# mk2.net
KiCad netlist of a schematic drawn in EAGLE
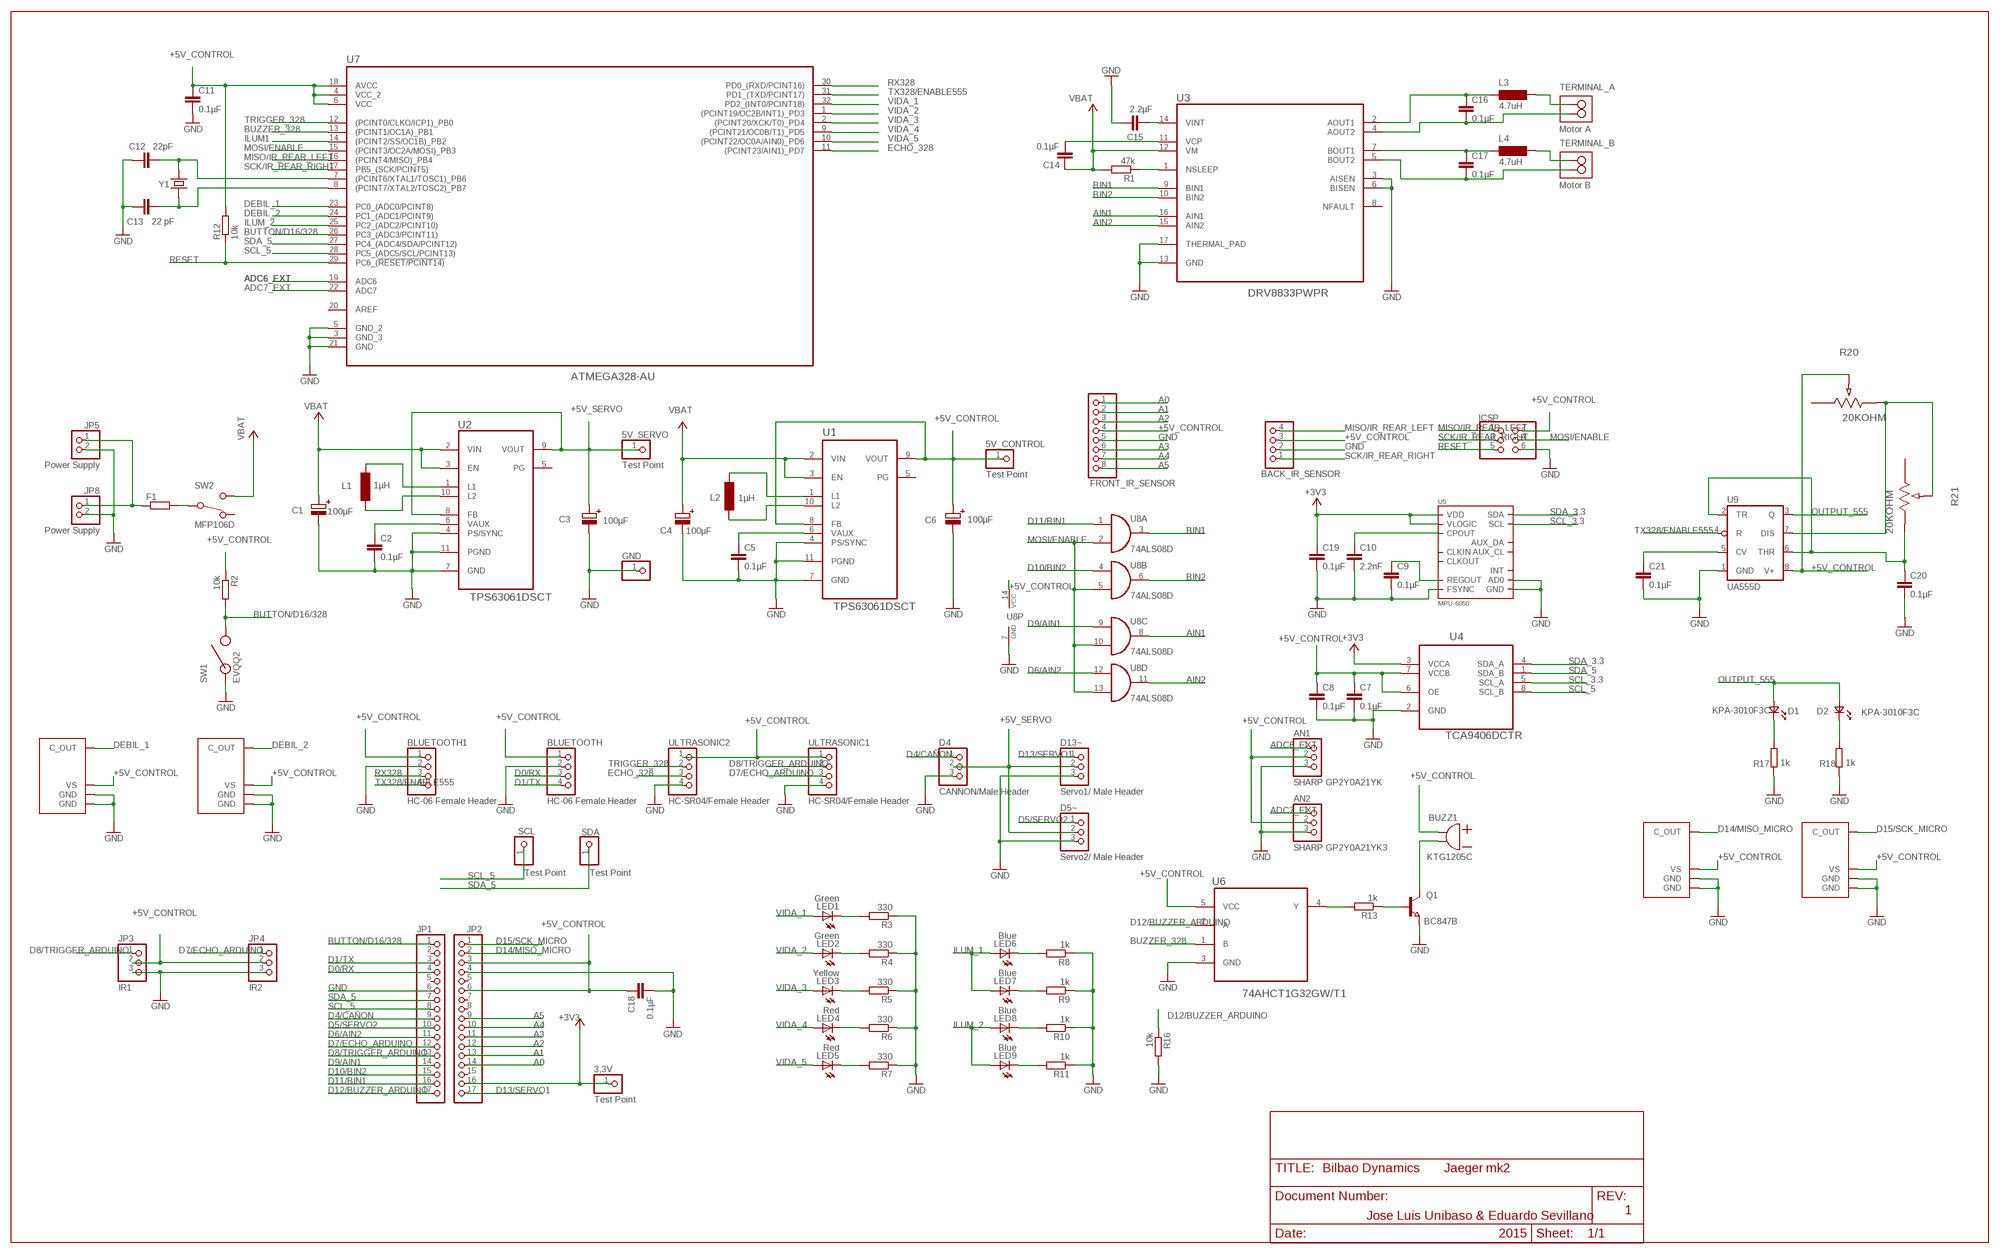
[diagram p0: schematic, sheet 1]

(export (version "E")
  (design (tool "Eeschema 10.0.6"))
  (components
    (comp (ref "3,3V")
      (value "Test Point")
      (footprint "eagle-import:1X01")
      (libsource (lib "eagle-import") (part "PINHD-1X1"))
    )
    (comp (ref "5V_CONTROL")
      (value "Test Point")
      (footprint "eagle-import:1X01")
      (libsource (lib "eagle-import") (part "PINHD-1X1"))
    )
    (comp (ref "5V_SERVO")
      (value "Test Point")
      (footprint "eagle-import:1X01")
      (libsource (lib "eagle-import") (part "PINHD-1X1"))
    )
    (comp (ref "AN1")
      (value "SHARP GP2Y0A21YK")
      (footprint "eagle-import:1X03")
      (libsource (lib "eagle-import") (part "PINHD-1X3"))
    )
    (comp (ref "AN2")
      (value "SHARP GP2Y0A21YK3")
      (footprint "eagle-import:1X03")
      (libsource (lib "eagle-import") (part "PINHD-1X3"))
    )
    (comp (ref "BACK_IR_SENSOR")
      (value "PINHD-1X4")
      (footprint "eagle-import:1X04")
      (libsource (lib "eagle-import") (part "PINHD-1X4"))
    )
    (comp (ref "BLUETOOTH")
      (value "HC-06 Female Header")
      (footprint "eagle-import:1X04")
      (libsource (lib "eagle-import") (part "PINHD-1X4"))
    )
    (comp (ref "BLUETOOTH1")
      (value "HC-06 Female Header")
      (footprint "eagle-import:1X04")
      (libsource (lib "eagle-import") (part "PINHD-1X4"))
    )
    (comp (ref "BUZZ1")
      (value "KTG1205C")
      (footprint "eagle-import:KTG1205C")
      (libsource (lib "eagle-import") (part "KTG1205C"))
    )
    (comp (ref "C1")
      (value "100µF")
      (footprint "eagle-import:EDK107M016A9G")
      (libsource (lib "eagle-import") (part "EDK107M016A9G"))
    )
    (comp (ref "C2")
      (value "0.1µF")
      (footprint "eagle-import:C0805K")
      (libsource (lib "eagle-import") (part "C-EUC0805K"))
    )
    (comp (ref "C3")
      (value "100µF")
      (footprint "eagle-import:EDK107M016A9G")
      (libsource (lib "eagle-import") (part "EDK107M016A9G"))
    )
    (comp (ref "C4")
      (value "100µF")
      (footprint "eagle-import:EDK107M016A9G")
      (libsource (lib "eagle-import") (part "EDK107M016A9G"))
    )
    (comp (ref "C5")
      (value "0.1µF")
      (footprint "eagle-import:C0805K")
      (libsource (lib "eagle-import") (part "C-EUC0805K"))
    )
    (comp (ref "C6")
      (value "100µF")
      (footprint "eagle-import:EDK107M016A9G")
      (libsource (lib "eagle-import") (part "EDK107M016A9G"))
    )
    (comp (ref "C7")
      (value "0.1µF")
      (footprint "eagle-import:C0805")
      (libsource (lib "eagle-import") (part "C-EUC0805"))
    )
    (comp (ref "C8")
      (value "0.1µF")
      (footprint "eagle-import:C0805")
      (libsource (lib "eagle-import") (part "C-EUC0805"))
    )
    (comp (ref "C9")
      (value "0.1µF")
      (footprint "eagle-import:C0805")
      (libsource (lib "eagle-import") (part "C-EUC0805"))
    )
    (comp (ref "C10")
      (value "2.2nF")
      (footprint "eagle-import:C0805")
      (libsource (lib "eagle-import") (part "C-EUC0805"))
    )
    (comp (ref "C11")
      (value "0.1µF")
      (footprint "eagle-import:C0805K")
      (libsource (lib "eagle-import") (part "C-EUC0805K"))
    )
    (comp (ref "C12")
      (value "22pF")
      (footprint "eagle-import:C0805K")
      (libsource (lib "eagle-import") (part "C-EUC0805K"))
    )
    (comp (ref "C13")
      (value "22 pF")
      (footprint "eagle-import:C0805K")
      (libsource (lib "eagle-import") (part "C-EUC0805K"))
    )
    (comp (ref "C14")
      (value "0.1µF")
      (footprint "eagle-import:C0805")
      (libsource (lib "eagle-import") (part "C-EUC0805"))
    )
    (comp (ref "C15")
      (value "2.2µF")
      (footprint "eagle-import:C0805")
      (libsource (lib "eagle-import") (part "C-EUC0805"))
    )
    (comp (ref "C16")
      (value "0.1µF")
      (footprint "eagle-import:C0805")
      (libsource (lib "eagle-import") (part "C-EUC0805"))
    )
    (comp (ref "C17")
      (value "0.1µF")
      (footprint "eagle-import:C0805")
      (libsource (lib "eagle-import") (part "C-EUC0805"))
    )
    (comp (ref "C18")
      (value "0.1µF")
      (footprint "eagle-import:C0805")
      (libsource (lib "eagle-import") (part "C-EUC0805"))
    )
    (comp (ref "C19")
      (value "0.1µF")
      (footprint "eagle-import:C0805")
      (libsource (lib "eagle-import") (part "C-EUC0805"))
    )
    (comp (ref "C20")
      (value "0.1µF")
      (footprint "eagle-import:C0805")
      (libsource (lib "eagle-import") (part "C-EUC0805"))
    )
    (comp (ref "C21")
      (value "0.1µF")
      (footprint "eagle-import:C0805")
      (libsource (lib "eagle-import") (part "C-EUC0805"))
    )
    (comp (ref "D1")
      (value "KPA-3010F3C")
      (footprint "eagle-import:KPA-3010F3C")
      (libsource (lib "eagle-import") (part "KPA-3010F3C"))
    )
    (comp (ref "D2")
      (value "KPA-3010F3C")
      (footprint "eagle-import:KPA-3010F3C")
      (libsource (lib "eagle-import") (part "KPA-3010F3C"))
    )
    (comp (ref "D4")
      (value "CANNON/Male Header")
      (footprint "eagle-import:1X03")
      (libsource (lib "eagle-import") (part "PINHD-1X3"))
    )
    (comp (ref "D5~")
      (value "Servo2/ Male Header")
      (footprint "eagle-import:1X03")
      (libsource (lib "eagle-import") (part "PINHD-1X3"))
    )
    (comp (ref "D13~")
      (value "Servo1/ Male Header")
      (footprint "eagle-import:1X03")
      (libsource (lib "eagle-import") (part "PINHD-1X3"))
    )
    (comp (ref "F1")
      (value "R-EU_R1206")
      (footprint "eagle-import:R1206")
      (libsource (lib "eagle-import") (part "R-EU_R1206"))
    )
    (comp (ref "FRONT_IR_SENSOR")
      (value "PINHD-1X8")
      (footprint "eagle-import:1X08")
      (libsource (lib "eagle-import") (part "PINHD-1X8"))
    )
    (comp (ref "GND")
      (value "PINHD-1X1")
      (footprint "eagle-import:1X01")
      (libsource (lib "eagle-import") (part "PINHD-1X1"))
    )
    (comp (ref "ICSP")
      (value "PINHD-2X3")
      (footprint "eagle-import:2X03")
      (libsource (lib "eagle-import") (part "PINHD-2X3"))
    )
    (comp (ref "IR_REC1")
      (value "TSMP77000TR")
      (footprint "eagle-import:TSMP77000TR")
      (libsource (lib "eagle-import") (part "TSMP77000TR"))
    )
    (comp (ref "IR_REC2")
      (value "TSMP77000TR")
      (footprint "eagle-import:TSMP77000TR")
      (libsource (lib "eagle-import") (part "TSMP77000TR"))
    )
    (comp (ref "IR_REC3")
      (value "TSMP77000TR")
      (footprint "eagle-import:TSMP77000TR")
      (libsource (lib "eagle-import") (part "TSMP77000TR"))
    )
    (comp (ref "IR_REC4")
      (value "TSMP77000TR")
      (footprint "eagle-import:TSMP77000TR")
      (libsource (lib "eagle-import") (part "TSMP77000TR"))
    )
    (comp (ref "JP1")
      (value "PINHD-1X17")
      (footprint "eagle-import:1X17")
      (libsource (lib "eagle-import") (part "PINHD-1X17"))
    )
    (comp (ref "JP2")
      (value "PINHD-1X17")
      (footprint "eagle-import:1X17")
      (libsource (lib "eagle-import") (part "PINHD-1X17"))
    )
    (comp (ref "JP3")
      (value "IR1")
      (footprint "eagle-import:1X03")
      (libsource (lib "eagle-import") (part "PINHD-1X3"))
    )
    (comp (ref "JP4")
      (value "IR2")
      (footprint "eagle-import:1X03")
      (libsource (lib "eagle-import") (part "PINHD-1X3"))
    )
    (comp (ref "JP5")
      (value "Power Supply")
      (footprint "eagle-import:1X02")
      (libsource (lib "eagle-import") (part "PINHD-1X2"))
    )
    (comp (ref "JP8")
      (value "Power Supply")
      (footprint "eagle-import:1X02")
      (libsource (lib "eagle-import") (part "PINHD-1X2"))
    )
    (comp (ref "L1")
      (value "1µH")
      (footprint "eagle-import:MCSDRH73B")
      (libsource (lib "eagle-import") (part "MCSDRH73B"))
    )
    (comp (ref "L2")
      (value "1µH")
      (footprint "eagle-import:MCSDRH73B")
      (libsource (lib "eagle-import") (part "MCSDRH73B"))
    )
    (comp (ref "L3")
      (value "4.7uH")
      (footprint "eagle-import:SRN4012T-4R7M")
      (libsource (lib "eagle-import") (part "SRN4012T-4R7M"))
    )
    (comp (ref "L4")
      (value "4.7uH")
      (footprint "eagle-import:SRN4012T-4R7M")
      (libsource (lib "eagle-import") (part "SRN4012T-4R7M"))
    )
    (comp (ref "LED1")
      (value "Green")
      (footprint "eagle-import:SML0805")
      (libsource (lib "eagle-import") (part "LEDSML0805"))
    )
    (comp (ref "LED2")
      (value "Green")
      (footprint "eagle-import:SML0805")
      (libsource (lib "eagle-import") (part "LEDSML0805"))
    )
    (comp (ref "LED3")
      (value "Yellow")
      (footprint "eagle-import:SML0805")
      (libsource (lib "eagle-import") (part "LEDSML0805"))
    )
    (comp (ref "LED4")
      (value "Red")
      (footprint "eagle-import:SML0805")
      (libsource (lib "eagle-import") (part "LEDSML0805"))
    )
    (comp (ref "LED5")
      (value "Red")
      (footprint "eagle-import:SML0805")
      (libsource (lib "eagle-import") (part "LEDSML0805"))
    )
    (comp (ref "LED6")
      (value "Blue")
      (footprint "eagle-import:SML0805")
      (libsource (lib "eagle-import") (part "LEDSML0805"))
    )
    (comp (ref "LED7")
      (value "Blue")
      (footprint "eagle-import:SML0805")
      (libsource (lib "eagle-import") (part "LEDSML0805"))
    )
    (comp (ref "LED8")
      (value "Blue")
      (footprint "eagle-import:SML0805")
      (libsource (lib "eagle-import") (part "LEDSML0805"))
    )
    (comp (ref "LED9")
      (value "Blue")
      (footprint "eagle-import:SML0805")
      (libsource (lib "eagle-import") (part "LEDSML0805"))
    )
    (comp (ref "Q1")
      (value "BC847B")
      (footprint "eagle-import:SOT23")
      (libsource (lib "eagle-import") (part "NPN-TRANSISTOR_SOT23"))
    )
    (comp (ref "R1")
      (value "47k")
      (footprint "eagle-import:R0805")
      (libsource (lib "eagle-import") (part "R-EU_R0805"))
    )
    (comp (ref "R2")
      (value "10k")
      (footprint "eagle-import:R0805")
      (libsource (lib "eagle-import") (part "R-EU_R0805"))
    )
    (comp (ref "R3")
      (value "330")
      (footprint "eagle-import:R0805")
      (libsource (lib "eagle-import") (part "R-EU_R0805"))
    )
    (comp (ref "R4")
      (value "330")
      (footprint "eagle-import:R0805")
      (libsource (lib "eagle-import") (part "R-EU_R0805"))
    )
    (comp (ref "R5")
      (value "330")
      (footprint "eagle-import:R0805")
      (libsource (lib "eagle-import") (part "R-EU_R0805"))
    )
    (comp (ref "R6")
      (value "330")
      (footprint "eagle-import:R0805")
      (libsource (lib "eagle-import") (part "R-EU_R0805"))
    )
    (comp (ref "R7")
      (value "330")
      (footprint "eagle-import:R0805")
      (libsource (lib "eagle-import") (part "R-EU_R0805"))
    )
    (comp (ref "R8")
      (value "1k")
      (footprint "eagle-import:R0805")
      (libsource (lib "eagle-import") (part "R-EU_R0805"))
    )
    (comp (ref "R9")
      (value "1k")
      (footprint "eagle-import:R0805")
      (libsource (lib "eagle-import") (part "R-EU_R0805"))
    )
    (comp (ref "R10")
      (value "1k")
      (footprint "eagle-import:R0805")
      (libsource (lib "eagle-import") (part "R-EU_R0805"))
    )
    (comp (ref "R11")
      (value "1k")
      (footprint "eagle-import:R0805")
      (libsource (lib "eagle-import") (part "R-EU_R0805"))
    )
    (comp (ref "R12")
      (value "10k")
      (footprint "eagle-import:R0805")
      (libsource (lib "eagle-import") (part "resistor_R-EU_R0805"))
    )
    (comp (ref "R13")
      (value "1k")
      (footprint "eagle-import:R0805")
      (libsource (lib "eagle-import") (part "R-EU_R0805"))
    )
    (comp (ref "R16")
      (value "10k")
      (footprint "eagle-import:R0805")
      (libsource (lib "eagle-import") (part "R-EU_R0805"))
    )
    (comp (ref "R17")
      (value "1k")
      (footprint "eagle-import:R0805")
      (libsource (lib "eagle-import") (part "R-EU_R0805"))
    )
    (comp (ref "R18")
      (value "1k")
      (footprint "eagle-import:R0805")
      (libsource (lib "eagle-import") (part "R-EU_R0805"))
    )
    (comp (ref "R20")
      (value "20KOHM")
      (footprint "eagle-import:POT_EVM2N")
      (fields (field (name "MPN") "EVM2NSX80B24") (field (name "TOLERANCE") "±25 %"))
      (libsource (lib "eagle-import") (part "EVM-2N2NSX80B24"))
    )
    (comp (ref "R21")
      (value "20KOHM")
      (footprint "eagle-import:POT_EVM2N")
      (fields (field (name "MPN") "EVM2NSX80B24") (field (name "TOLERANCE") "±25 %"))
      (libsource (lib "eagle-import") (part "EVM-2N2NSX80B24"))
    )
    (comp (ref "SCL")
      (value "Test Point")
      (footprint "eagle-import:1X01")
      (libsource (lib "eagle-import") (part "PINHD-1X1"))
    )
    (comp (ref "SDA")
      (value "Test Point")
      (footprint "eagle-import:1X01")
      (libsource (lib "eagle-import") (part "PINHD-1X1"))
    )
    (comp (ref "SW1")
      (value "EVQQ2")
      (footprint "eagle-import:EVQQ2")
      (libsource (lib "eagle-import") (part "EVQQ2"))
    )
    (comp (ref "SW2")
      (value "MFP106D")
      (footprint "eagle-import:MFP106D")
      (libsource (lib "eagle-import") (part "MFP106D"))
    )
    (comp (ref "TERMINAL_A")
      (value "Motor A")
      (footprint "eagle-import:CTB30512BK")
      (libsource (lib "eagle-import") (part "CTB30512BK"))
    )
    (comp (ref "TERMINAL_B")
      (value "Motor B")
      (footprint "eagle-import:CTB30512BK")
      (libsource (lib "eagle-import") (part "CTB30512BK"))
    )
    (comp (ref "U1")
      (value "TPS63061DSCT")
      (footprint "eagle-import:SON50P300X300X80-11N")
      (libsource (lib "eagle-import") (part "TPS63061DSCT"))
    )
    (comp (ref "U2")
      (value "TPS63061DSCT")
      (footprint "eagle-import:SON50P300X300X80-11N")
      (libsource (lib "eagle-import") (part "TPS63061DSCT"))
    )
    (comp (ref "U3")
      (value "DRV8833PWPR")
      (footprint "eagle-import:SOP65P640X120-17N")
      (libsource (lib "eagle-import") (part "DRV8833PWPR"))
    )
    (comp (ref "U4")
      (value "TCA9406DCTR")
      (footprint "eagle-import:SOP65P400X130-8N")
      (libsource (lib "eagle-import") (part "TCA9406DCTR"))
    )
    (comp (ref "U5")
      (value "MPU-6050")
      (footprint "eagle-import:QFN.24.4X4")
      (libsource (lib "eagle-import") (part "MPU-6050"))
    )
    (comp (ref "U6")
      (value "74AHCT1G32GW/T1")
      (footprint "eagle-import:SOT65P210X110-5N")
      (libsource (lib "eagle-import") (part "74AHCT1G32GW/T1"))
    )
    (comp (ref "U7")
      (value "ATMEGA328-AU")
      (footprint "eagle-import:QFP80P900X900X120-32N")
      (libsource (lib "eagle-import") (part "ATMEGA328-AU"))
    )
    (comp (ref "U8")
      (value "74ALS08D")
      (footprint "eagle-import:SO14")
      (libsource (lib "eagle-import") (part "7408DALS"))
    )
    (comp (ref "U9")
      (value "UA555D")
      (footprint "eagle-import:SO08")
      (libsource (lib "eagle-import") (part "555DUA"))
    )
    (comp (ref "ULTRASONIC1")
      (value "HC-SR04/Female Header")
      (footprint "eagle-import:1X04")
      (libsource (lib "eagle-import") (part "PINHD-1X4"))
    )
    (comp (ref "ULTRASONIC2")
      (value "HC-SR04/Female Header")
      (footprint "eagle-import:1X04")
      (libsource (lib "eagle-import") (part "PINHD-1X4"))
    )
    (comp (ref "Y1")
      (value "E3SB16.0000F09G11AE")
      (footprint "eagle-import:E3SB16.0000F09G11A")
      (libsource (lib "eagle-import") (part "E3SB16.0000F09G11AE"))
    )
  )
  (nets
    (net (code "1") (name "+3V3") (class "Default")
      (node (ref "3,3V") (pin "1") (pinfunction "1_1") (pintype "passive"))
      (node (ref "JP2") (pin "16") (pinfunction "16_16") (pintype "passive"))
      (node (ref "U4") (pin "3") (pinfunction "VCCA_3") (pintype "power_in"))
    )
    (net (code "2") (name "/+5V_CONTROL") (class "Default")
      (node (ref "5V_CONTROL") (pin "1") (pinfunction "1_1") (pintype "passive"))
      (node (ref "AN1") (pin "2") (pinfunction "2_2") (pintype "passive"))
      (node (ref "AN2") (pin "2") (pinfunction "2_2") (pintype "passive"))
      (node (ref "BACK_IR_SENSOR") (pin "3") (pinfunction "3_3") (pintype "passive"))
      (node (ref "BLUETOOTH") (pin "1") (pinfunction "1_1") (pintype "passive"))
      (node (ref "BLUETOOTH1") (pin "1") (pinfunction "1_1") (pintype "passive"))
      (node (ref "BUZZ1") (pin "+") (pinfunction "+_+") (pintype "passive"))
      (node (ref "C11") (pin "1") (pinfunction "1_1") (pintype "passive"))
      (node (ref "C18") (pin "1") (pinfunction "1_1") (pintype "passive"))
      (node (ref "C6") (pin "1") (pinfunction "1_1") (pintype "passive"))
      (node (ref "C7") (pin "1") (pinfunction "1_1") (pintype "passive"))
      (node (ref "C8") (pin "1") (pinfunction "1_1") (pintype "passive"))
      (node (ref "FRONT_IR_SENSOR") (pin "4") (pinfunction "4_4") (pintype "passive"))
      (node (ref "ICSP") (pin "2") (pinfunction "2_2") (pintype "passive"))
      (node (ref "IR_REC1") (pin "2") (pinfunction "VS_2") (pintype "power_in"))
      (node (ref "IR_REC2") (pin "2") (pinfunction "VS_2") (pintype "power_in"))
      (node (ref "IR_REC3") (pin "2") (pinfunction "VS_2") (pintype "power_in"))
      (node (ref "IR_REC4") (pin "2") (pinfunction "VS_2") (pintype "power_in"))
      (node (ref "JP2") (pin "3") (pinfunction "3_3") (pintype "passive"))
      (node (ref "JP2") (pin "6") (pinfunction "6_6") (pintype "passive"))
      (node (ref "JP3") (pin "2") (pinfunction "2_2") (pintype "passive"))
      (node (ref "JP4") (pin "2") (pinfunction "2_2") (pintype "passive"))
      (node (ref "R12") (pin "2") (pinfunction "2_2") (pintype "passive"))
      (node (ref "R2") (pin "1") (pinfunction "1_1") (pintype "passive"))
      (node (ref "R20") (pin "2") (pinfunction "2_2") (pintype "passive"))
      (node (ref "U1") (pin "8") (pinfunction "FB_8") (pintype "input"))
      (node (ref "U1") (pin "9") (pinfunction "VOUT_9") (pintype "output"))
      (node (ref "U4") (pin "6") (pinfunction "OE_6") (pintype "input"))
      (node (ref "U4") (pin "7") (pinfunction "VCCB_7") (pintype "power_in"))
      (node (ref "U6") (pin "5") (pinfunction "VCC_5") (pintype "power_in"))
      (node (ref "U7") (pin "18") (pinfunction "AVCC_18") (pintype "power_in"))
      (node (ref "U7") (pin "4") (pinfunction "VCC_2_4") (pintype "power_in"))
      (node (ref "U7") (pin "6") (pinfunction "VCC_6") (pintype "power_in"))
      (node (ref "U8") (pin "14") (pinfunction "VCC_14") (pintype "power_in"))
      (node (ref "U9") (pin "8") (pinfunction "V+_8") (pintype "power_in"))
      (node (ref "ULTRASONIC1") (pin "1") (pinfunction "1_1") (pintype "passive"))
      (node (ref "ULTRASONIC2") (pin "1") (pinfunction "1_1") (pintype "passive"))
    )
    (net (code "3") (name "/+5V_SERVO") (class "Default")
      (node (ref "5V_SERVO") (pin "1") (pinfunction "1_1") (pintype "passive"))
      (node (ref "C3") (pin "1") (pinfunction "1_1") (pintype "passive"))
      (node (ref "D13~") (pin "2") (pinfunction "2_2") (pintype "passive"))
      (node (ref "D4") (pin "2") (pinfunction "2_2") (pintype "passive"))
      (node (ref "D5~") (pin "2") (pinfunction "2_2") (pintype "passive"))
      (node (ref "U2") (pin "8") (pinfunction "FB_8") (pintype "input"))
      (node (ref "U2") (pin "9") (pinfunction "VOUT_9") (pintype "output"))
    )
    (net (code "4") (name "/A0") (class "Default")
      (node (ref "FRONT_IR_SENSOR") (pin "1") (pinfunction "1_1") (pintype "passive"))
      (node (ref "JP2") (pin "14") (pinfunction "14_14") (pintype "passive"))
    )
    (net (code "5") (name "/A1") (class "Default")
      (node (ref "FRONT_IR_SENSOR") (pin "2") (pinfunction "2_2") (pintype "passive"))
      (node (ref "JP2") (pin "13") (pinfunction "13_13") (pintype "passive"))
    )
    (net (code "6") (name "/A2") (class "Default")
      (node (ref "FRONT_IR_SENSOR") (pin "3") (pinfunction "3_3") (pintype "passive"))
      (node (ref "JP2") (pin "12") (pinfunction "12_12") (pintype "passive"))
    )
    (net (code "7") (name "/A3") (class "Default")
      (node (ref "FRONT_IR_SENSOR") (pin "6") (pinfunction "6_6") (pintype "passive"))
      (node (ref "JP2") (pin "11") (pinfunction "11_11") (pintype "passive"))
    )
    (net (code "8") (name "/A4") (class "Default")
      (node (ref "FRONT_IR_SENSOR") (pin "7") (pinfunction "7_7") (pintype "passive"))
      (node (ref "JP2") (pin "10") (pinfunction "10_10") (pintype "passive"))
    )
    (net (code "9") (name "/A5") (class "Default")
      (node (ref "FRONT_IR_SENSOR") (pin "8") (pinfunction "8_8") (pintype "passive"))
      (node (ref "JP2") (pin "9") (pinfunction "9_9") (pintype "passive"))
    )
    (net (code "10") (name "/ADC6_EXT") (class "Default")
      (node (ref "AN1") (pin "1") (pinfunction "1_1") (pintype "passive"))
      (node (ref "U7") (pin "19") (pinfunction "ADC6_19") (pintype "input"))
    )
    (net (code "11") (name "/ADC7_EXT") (class "Default")
      (node (ref "AN2") (pin "1") (pinfunction "1_1") (pintype "passive"))
      (node (ref "U7") (pin "22") (pinfunction "ADC7_22") (pintype "input"))
    )
    (net (code "12") (name "/AIN1") (class "Default")
      (node (ref "U3") (pin "16") (pinfunction "AIN1_16") (pintype "input"))
      (node (ref "U8") (pin "8") (pinfunction "O_8") (pintype "output"))
    )
    (net (code "13") (name "/AIN2") (class "Default")
      (node (ref "U3") (pin "15") (pinfunction "AIN2_15") (pintype "input"))
      (node (ref "U8") (pin "11") (pinfunction "O_11") (pintype "output"))
    )
    (net (code "14") (name "/BIN1") (class "Default")
      (node (ref "U3") (pin "9") (pinfunction "BIN1_9") (pintype "input"))
      (node (ref "U8") (pin "3") (pinfunction "O_3") (pintype "output"))
    )
    (net (code "15") (name "/BIN2") (class "Default")
      (node (ref "U3") (pin "10") (pinfunction "BIN2_10") (pintype "input"))
      (node (ref "U8") (pin "6") (pinfunction "O_6") (pintype "output"))
    )
    (net (code "16") (name "/BUTTON{slash}D16{slash}328") (class "Default")
      (node (ref "JP1") (pin "1") (pinfunction "1_1") (pintype "passive"))
      (node (ref "R2") (pin "2") (pinfunction "2_2") (pintype "passive"))
      (node (ref "SW1") (pin "P$1") (pinfunction "P$2_P$1") (pintype "passive"))
      (node (ref "SW1") (pin "P$4") (pinfunction "P$2_P$4") (pintype "passive"))
      (node (ref "U7") (pin "26") (pinfunction "PC3_(ADC3/PCINT11)_26") (pintype "bidirectional"))
    )
    (net (code "17") (name "/BUZZER_328") (class "Default")
      (node (ref "U6") (pin "1") (pinfunction "B_1") (pintype "input"))
      (node (ref "U7") (pin "13") (pinfunction "(PCINT1/OC1A)_PB1_13") (pintype "bidirectional"))
    )
    (net (code "18") (name "/D0{slash}RX") (class "Default")
      (node (ref "BLUETOOTH") (pin "3") (pinfunction "3_3") (pintype "passive"))
      (node (ref "JP1") (pin "4") (pinfunction "4_4") (pintype "passive"))
    )
    (net (code "19") (name "/D1{slash}TX") (class "Default")
      (node (ref "BLUETOOTH") (pin "4") (pinfunction "4_4") (pintype "passive"))
      (node (ref "JP1") (pin "3") (pinfunction "3_3") (pintype "passive"))
    )
    (net (code "20") (name "/D4{slash}CAÑON") (class "Default")
      (node (ref "D4") (pin "1") (pinfunction "1_1") (pintype "passive"))
      (node (ref "JP1") (pin "9") (pinfunction "9_9") (pintype "passive"))
    )
    (net (code "21") (name "/D5{slash}SERVO2") (class "Default")
      (node (ref "D5~") (pin "1") (pinfunction "1_1") (pintype "passive"))
      (node (ref "JP1") (pin "10") (pinfunction "10_10") (pintype "passive"))
    )
    (net (code "22") (name "/D6{slash}AIN2") (class "Default")
      (node (ref "JP1") (pin "11") (pinfunction "11_11") (pintype "passive"))
      (node (ref "U8") (pin "12") (pinfunction "I0_12") (pintype "input"))
    )
    (net (code "23") (name "/D7{slash}ECHO_ARDUINO") (class "Default")
      (node (ref "JP1") (pin "12") (pinfunction "12_12") (pintype "passive"))
      (node (ref "JP4") (pin "1") (pinfunction "1_1") (pintype "passive"))
      (node (ref "ULTRASONIC1") (pin "3") (pinfunction "3_3") (pintype "passive"))
    )
    (net (code "24") (name "/D8{slash}TRIGGER_ARDUINO") (class "Default")
      (node (ref "JP1") (pin "13") (pinfunction "13_13") (pintype "passive"))
      (node (ref "JP3") (pin "1") (pinfunction "1_1") (pintype "passive"))
      (node (ref "ULTRASONIC1") (pin "2") (pinfunction "2_2") (pintype "passive"))
    )
    (net (code "25") (name "/D9{slash}AIN1") (class "Default")
      (node (ref "JP1") (pin "14") (pinfunction "14_14") (pintype "passive"))
      (node (ref "U8") (pin "9") (pinfunction "I0_9") (pintype "input"))
    )
    (net (code "26") (name "/D10{slash}BIN2") (class "Default")
      (node (ref "JP1") (pin "15") (pinfunction "15_15") (pintype "passive"))
      (node (ref "U8") (pin "4") (pinfunction "I0_4") (pintype "input"))
    )
    (net (code "27") (name "/D11{slash}BIN1") (class "Default")
      (node (ref "JP1") (pin "16") (pinfunction "16_16") (pintype "passive"))
      (node (ref "U8") (pin "1") (pinfunction "I0_1") (pintype "input"))
    )
    (net (code "28") (name "/D12{slash}BUZZER_ARDUINO") (class "Default")
      (node (ref "JP1") (pin "17") (pinfunction "17_17") (pintype "passive"))
      (node (ref "R16") (pin "1") (pinfunction "1_1") (pintype "passive"))
      (node (ref "U6") (pin "2") (pinfunction "A_2") (pintype "input"))
    )
    (net (code "29") (name "/D13{slash}SERVO1") (class "Default")
      (node (ref "D13~") (pin "1") (pinfunction "1_1") (pintype "passive"))
      (node (ref "JP2") (pin "17") (pinfunction "17_17") (pintype "passive"))
    )
    (net (code "30") (name "/D14{slash}MISO_MICRO") (class "Default")
      (node (ref "IR_REC1") (pin "3") (pinfunction "C_OUT_3") (pintype "bidirectional"))
      (node (ref "JP2") (pin "2") (pinfunction "2_2") (pintype "passive"))
    )
    (net (code "31") (name "/D15{slash}SCK_MICRO") (class "Default")
      (node (ref "IR_REC2") (pin "3") (pinfunction "C_OUT_3") (pintype "bidirectional"))
      (node (ref "JP2") (pin "1") (pinfunction "1_1") (pintype "passive"))
    )
    (net (code "32") (name "/DEBIL_1") (class "Default")
      (node (ref "IR_REC3") (pin "3") (pinfunction "C_OUT_3") (pintype "bidirectional"))
      (node (ref "U7") (pin "23") (pinfunction "PC0_(ADC0/PCINT8)_23") (pintype "bidirectional"))
    )
    (net (code "33") (name "/DEBIL_2") (class "Default")
      (node (ref "IR_REC4") (pin "3") (pinfunction "C_OUT_3") (pintype "bidirectional"))
      (node (ref "U7") (pin "24") (pinfunction "PC1_(ADC1/PCINT9)_24") (pintype "bidirectional"))
    )
    (net (code "34") (name "/ECHO_328") (class "Default")
      (node (ref "U7") (pin "11") (pinfunction "(PCINT23/AIN1)_PD7_11") (pintype "bidirectional"))
      (node (ref "ULTRASONIC2") (pin "3") (pinfunction "3_3") (pintype "passive"))
    )
    (net (code "35") (name "/ILUM1") (class "Default")
      (node (ref "U7") (pin "14") (pinfunction "(PCINT2/SS/OC1B)_PB2_14") (pintype "bidirectional"))
    )
    (net (code "36") (name "/ILUM_1") (class "Default")
      (node (ref "LED6") (pin "A") (pinfunction "A_A") (pintype "passive"))
      (node (ref "LED7") (pin "A") (pinfunction "A_A") (pintype "passive"))
    )
    (net (code "37") (name "/ILUM_2") (class "Default")
      (node (ref "LED8") (pin "A") (pinfunction "A_A") (pintype "passive"))
      (node (ref "LED9") (pin "A") (pinfunction "A_A") (pintype "passive"))
      (node (ref "U7") (pin "25") (pinfunction "PC2_(ADC2/PCINT10)_25") (pintype "bidirectional"))
    )
    (net (code "38") (name "/MISO{slash}IR_REAR_LEFT") (class "Default")
      (node (ref "BACK_IR_SENSOR") (pin "4") (pinfunction "4_4") (pintype "passive"))
      (node (ref "ICSP") (pin "1") (pinfunction "1_1") (pintype "passive"))
      (node (ref "U7") (pin "16") (pinfunction "(PCINT4/MISO)_PB4_16") (pintype "bidirectional"))
    )
    (net (code "39") (name "/MOSI{slash}ENABLE") (class "Default")
      (node (ref "ICSP") (pin "4") (pinfunction "4_4") (pintype "passive"))
      (node (ref "U7") (pin "15") (pinfunction "(PCINT3/OC2A/MOSI)_PB3_15") (pintype "bidirectional"))
      (node (ref "U8") (pin "10") (pinfunction "I1_10") (pintype "input"))
      (node (ref "U8") (pin "13") (pinfunction "I1_13") (pintype "input"))
      (node (ref "U8") (pin "2") (pinfunction "I1_2") (pintype "input"))
      (node (ref "U8") (pin "5") (pinfunction "I1_5") (pintype "input"))
    )
    (net (code "40") (name "/OUTPUT_555") (class "Default")
      (node (ref "D1") (pin "A") (pinfunction "A_A") (pintype "passive"))
      (node (ref "D2") (pin "A") (pinfunction "A_A") (pintype "passive"))
      (node (ref "U9") (pin "3") (pinfunction "Q_3") (pintype "output"))
    )
    (net (code "41") (name "/RESET") (class "Default")
      (node (ref "ICSP") (pin "5") (pinfunction "5_5") (pintype "passive"))
      (node (ref "R12") (pin "1") (pinfunction "1_1") (pintype "passive"))
      (node (ref "U7") (pin "29") (pinfunction "PC6_(~{RESET/PCINT14})_29") (pintype "bidirectional"))
    )
    (net (code "42") (name "/RX328") (class "Default")
      (node (ref "BLUETOOTH1") (pin "3") (pinfunction "3_3") (pintype "passive"))
      (node (ref "U7") (pin "30") (pinfunction "PD0_(RXD/PCINT16)_30") (pintype "bidirectional"))
    )
    (net (code "43") (name "/SCK{slash}IR_REAR_RIGHT") (class "Default")
      (node (ref "BACK_IR_SENSOR") (pin "1") (pinfunction "1_1") (pintype "passive"))
      (node (ref "ICSP") (pin "3") (pinfunction "3_3") (pintype "passive"))
      (node (ref "U7") (pin "17") (pinfunction "PB5_(SCK/PCINT5)_17") (pintype "bidirectional"))
    )
    (net (code "44") (name "/SCL_3.3") (class "Default")
      (node (ref "U4") (pin "5") (pinfunction "SCL_A_5") (pintype "bidirectional"))
      (node (ref "U5") (pin "23") (pinfunction "SCL_23") (pintype "bidirectional"))
    )
    (net (code "45") (name "/SCL_5") (class "Default")
      (node (ref "JP1") (pin "8") (pinfunction "8_8") (pintype "passive"))
      (node (ref "SCL") (pin "1") (pinfunction "1_1") (pintype "passive"))
      (node (ref "U4") (pin "8") (pinfunction "SCL_B_8") (pintype "bidirectional"))
      (node (ref "U7") (pin "28") (pinfunction "PC5_(ADC5/SCL/PCINT13)_28") (pintype "bidirectional"))
    )
    (net (code "46") (name "/SDA_3.3") (class "Default")
      (node (ref "U4") (pin "4") (pinfunction "SDA_A_4") (pintype "bidirectional"))
      (node (ref "U5") (pin "24") (pinfunction "SDA_24") (pintype "bidirectional"))
    )
    (net (code "47") (name "/SDA_5") (class "Default")
      (node (ref "JP1") (pin "7") (pinfunction "7_7") (pintype "passive"))
      (node (ref "SDA") (pin "1") (pinfunction "1_1") (pintype "passive"))
      (node (ref "U4") (pin "1") (pinfunction "SDA_B_1") (pintype "bidirectional"))
      (node (ref "U7") (pin "27") (pinfunction "PC4_(ADC4/SDA/PCINT12)_27") (pintype "bidirectional"))
    )
    (net (code "48") (name "/TRIGGER_328") (class "Default")
      (node (ref "U7") (pin "12") (pinfunction "(PCINT0/CLKO/ICP1)_PB0_12") (pintype "bidirectional"))
      (node (ref "ULTRASONIC2") (pin "2") (pinfunction "2_2") (pintype "passive"))
    )
    (net (code "49") (name "/TX328{slash}ENABLE555") (class "Default")
      (node (ref "BLUETOOTH1") (pin "4") (pinfunction "4_4") (pintype "passive"))
      (node (ref "U7") (pin "31") (pinfunction "PD1_(TXD/PCINT17)_31") (pintype "bidirectional"))
      (node (ref "U9") (pin "4") (pinfunction "R_4") (pintype "input"))
    )
    (net (code "50") (name "/VIDA_1") (class "Default")
      (node (ref "LED1") (pin "A") (pinfunction "A_A") (pintype "passive"))
      (node (ref "U7") (pin "32") (pinfunction "PD2_(INT0/PCINT18)_32") (pintype "bidirectional"))
    )
    (net (code "51") (name "/VIDA_2") (class "Default")
      (node (ref "LED2") (pin "A") (pinfunction "A_A") (pintype "passive"))
      (node (ref "U7") (pin "1") (pinfunction "(PCINT19/OC2B/INT1)_PD3_1") (pintype "bidirectional"))
    )
    (net (code "52") (name "/VIDA_3") (class "Default")
      (node (ref "LED3") (pin "A") (pinfunction "A_A") (pintype "passive"))
      (node (ref "U7") (pin "2") (pinfunction "(PCINT20/XCK/T0)_PD4_2") (pintype "bidirectional"))
    )
    (net (code "53") (name "/VIDA_4") (class "Default")
      (node (ref "LED4") (pin "A") (pinfunction "A_A") (pintype "passive"))
      (node (ref "U7") (pin "9") (pinfunction "(PCINT21/OC0B/T1)_PD5_9") (pintype "bidirectional"))
    )
    (net (code "54") (name "/VIDA_5") (class "Default")
      (node (ref "LED5") (pin "A") (pinfunction "A_A") (pintype "passive"))
      (node (ref "U7") (pin "10") (pinfunction "(PCINT22/OC0A/AIN0)_PD6_10") (pintype "bidirectional"))
    )
    (net (code "55") (name "GND") (class "Default")
      (node (ref "AN1") (pin "3") (pinfunction "3_3") (pintype "passive"))
      (node (ref "AN2") (pin "3") (pinfunction "3_3") (pintype "passive"))
      (node (ref "BACK_IR_SENSOR") (pin "2") (pinfunction "2_2") (pintype "passive"))
      (node (ref "BLUETOOTH") (pin "2") (pinfunction "2_2") (pintype "passive"))
      (node (ref "BLUETOOTH1") (pin "2") (pinfunction "2_2") (pintype "passive"))
      (node (ref "C1") (pin "2") (pinfunction "2_2") (pintype "passive"))
      (node (ref "C10") (pin "2") (pinfunction "2_2") (pintype "passive"))
      (node (ref "C11") (pin "2") (pinfunction "2_2") (pintype "passive"))
      (node (ref "C12") (pin "1") (pinfunction "1_1") (pintype "passive"))
      (node (ref "C13") (pin "1") (pinfunction "1_1") (pintype "passive"))
      (node (ref "C15") (pin "1") (pinfunction "1_1") (pintype "passive"))
      (node (ref "C18") (pin "2") (pinfunction "2_2") (pintype "passive"))
      (node (ref "C19") (pin "2") (pinfunction "2_2") (pintype "passive"))
      (node (ref "C2") (pin "2") (pinfunction "2_2") (pintype "passive"))
      (node (ref "C20") (pin "2") (pinfunction "2_2") (pintype "passive"))
      (node (ref "C21") (pin "2") (pinfunction "2_2") (pintype "passive"))
      (node (ref "C3") (pin "2") (pinfunction "2_2") (pintype "passive"))
      (node (ref "C4") (pin "2") (pinfunction "2_2") (pintype "passive"))
      (node (ref "C5") (pin "2") (pinfunction "2_2") (pintype "passive"))
      (node (ref "C6") (pin "2") (pinfunction "2_2") (pintype "passive"))
      (node (ref "C7") (pin "2") (pinfunction "2_2") (pintype "passive"))
      (node (ref "C8") (pin "2") (pinfunction "2_2") (pintype "passive"))
      (node (ref "C9") (pin "2") (pinfunction "2_2") (pintype "passive"))
      (node (ref "D13~") (pin "3") (pinfunction "3_3") (pintype "passive"))
      (node (ref "D4") (pin "3") (pinfunction "3_3") (pintype "passive"))
      (node (ref "D5~") (pin "3") (pinfunction "3_3") (pintype "passive"))
      (node (ref "FRONT_IR_SENSOR") (pin "5") (pinfunction "5_5") (pintype "passive"))
      (node (ref "GND") (pin "1") (pinfunction "1_1") (pintype "passive"))
      (node (ref "ICSP") (pin "6") (pinfunction "6_6") (pintype "passive"))
      (node (ref "IR_REC1") (pin "1") (pinfunction "GND_1") (pintype "power_in"))
      (node (ref "IR_REC1") (pin "4") (pinfunction "GND_4") (pintype "power_in"))
      (node (ref "IR_REC2") (pin "1") (pinfunction "GND_1") (pintype "power_in"))
      (node (ref "IR_REC2") (pin "4") (pinfunction "GND_4") (pintype "power_in"))
      (node (ref "IR_REC3") (pin "1") (pinfunction "GND_1") (pintype "power_in"))
      (node (ref "IR_REC3") (pin "4") (pinfunction "GND_4") (pintype "power_in"))
      (node (ref "IR_REC4") (pin "1") (pinfunction "GND_1") (pintype "power_in"))
      (node (ref "IR_REC4") (pin "4") (pinfunction "GND_4") (pintype "power_in"))
      (node (ref "JP1") (pin "6") (pinfunction "6_6") (pintype "passive"))
      (node (ref "JP2") (pin "4") (pinfunction "4_4") (pintype "passive"))
      (node (ref "JP3") (pin "3") (pinfunction "3_3") (pintype "passive"))
      (node (ref "JP4") (pin "3") (pinfunction "3_3") (pintype "passive"))
      (node (ref "JP5") (pin "2") (pinfunction "2_2") (pintype "passive"))
      (node (ref "JP8") (pin "2") (pinfunction "2_2") (pintype "passive"))
      (node (ref "Q1") (pin "2") (pinfunction "E_2") (pintype "passive"))
      (node (ref "R10") (pin "1") (pinfunction "1_1") (pintype "passive"))
      (node (ref "R11") (pin "1") (pinfunction "1_1") (pintype "passive"))
      (node (ref "R16") (pin "2") (pinfunction "2_2") (pintype "passive"))
      (node (ref "R17") (pin "2") (pinfunction "2_2") (pintype "passive"))
      (node (ref "R18") (pin "2") (pinfunction "2_2") (pintype "passive"))
      (node (ref "R3") (pin "1") (pinfunction "1_1") (pintype "passive"))
      (node (ref "R4") (pin "1") (pinfunction "1_1") (pintype "passive"))
      (node (ref "R5") (pin "1") (pinfunction "1_1") (pintype "passive"))
      (node (ref "R6") (pin "1") (pinfunction "1_1") (pintype "passive"))
      (node (ref "R7") (pin "1") (pinfunction "1_1") (pintype "passive"))
      (node (ref "R8") (pin "1") (pinfunction "1_1") (pintype "passive"))
      (node (ref "R9") (pin "1") (pinfunction "1_1") (pintype "passive"))
      (node (ref "SW1") (pin "P$2") (pinfunction "P$1_P$2") (pintype "passive"))
      (node (ref "SW1") (pin "P$3") (pinfunction "P$1_P$3") (pintype "passive"))
      (node (ref "U1") (pin "11") (pinfunction "PGND_11") (pintype "passive"))
      (node (ref "U1") (pin "4") (pinfunction "PS/SYNC_4") (pintype "input"))
      (node (ref "U1") (pin "7") (pinfunction "GND_7") (pintype "passive"))
      (node (ref "U2") (pin "11") (pinfunction "PGND_11") (pintype "passive"))
      (node (ref "U2") (pin "4") (pinfunction "PS/SYNC_4") (pintype "input"))
      (node (ref "U2") (pin "7") (pinfunction "GND_7") (pintype "passive"))
      (node (ref "U3") (pin "13") (pinfunction "GND_13") (pintype "passive"))
      (node (ref "U3") (pin "17") (pinfunction "THERMAL_PAD_17") (pintype "passive"))
      (node (ref "U3") (pin "3") (pinfunction "AISEN_3") (pintype "bidirectional"))
      (node (ref "U3") (pin "6") (pinfunction "BISEN_6") (pintype "bidirectional"))
      (node (ref "U4") (pin "2") (pinfunction "GND_2") (pintype "power_in"))
      (node (ref "U5") (pin "11") (pinfunction "FSYNC_11") (pintype "bidirectional"))
      (node (ref "U5") (pin "18") (pinfunction "GND_18") (pintype "bidirectional"))
      (node (ref "U5") (pin "9") (pinfunction "AD0_9") (pintype "bidirectional"))
      (node (ref "U6") (pin "3") (pinfunction "GND_3") (pintype "passive"))
      (node (ref "U7") (pin "21") (pinfunction "GND_21") (pintype "passive"))
      (node (ref "U7") (pin "3") (pinfunction "GND_3_3") (pintype "passive"))
      (node (ref "U7") (pin "5") (pinfunction "GND_2_5") (pintype "passive"))
      (node (ref "U8") (pin "7") (pinfunction "GND_7") (pintype "power_in"))
      (node (ref "U9") (pin "1") (pinfunction "GND_1") (pintype "power_in"))
      (node (ref "ULTRASONIC1") (pin "4") (pinfunction "4_4") (pintype "passive"))
      (node (ref "ULTRASONIC2") (pin "4") (pinfunction "4_4") (pintype "passive"))
    )
    (net (code "56") (name "Net-(D1-PadC)") (class "Default")
      (node (ref "D1") (pin "C") (pinfunction "C_C") (pintype "passive"))
      (node (ref "R17") (pin "1") (pinfunction "1_1") (pintype "passive"))
    )
    (net (code "57") (name "Net-(D2-PadC)") (class "Default")
      (node (ref "D2") (pin "C") (pinfunction "C_C") (pintype "passive"))
      (node (ref "R18") (pin "1") (pinfunction "1_1") (pintype "passive"))
    )
    (net (code "58") (name "Net-(F1-Pad1)") (class "Default")
      (node (ref "F1") (pin "1") (pinfunction "1_1") (pintype "passive"))
      (node (ref "JP5") (pin "1") (pinfunction "1_1") (pintype "passive"))
      (node (ref "JP8") (pin "1") (pinfunction "1_1") (pintype "passive"))
    )
    (net (code "59") (name "Net-(F1-Pad2)") (class "Default")
      (node (ref "F1") (pin "2") (pinfunction "2_2") (pintype "passive"))
      (node (ref "SW2") (pin "COM") (pinfunction "COM_COM") (pintype "passive"))
    )
    (net (code "60") (name "Net-(L1-P$1)") (class "Default")
      (node (ref "L1") (pin "1") (pinfunction "P$1_1") (pintype "passive"))
      (node (ref "U2") (pin "10") (pinfunction "L2_10") (pintype "input"))
    )
    (net (code "61") (name "Net-(L1-P$2)") (class "Default")
      (node (ref "L1") (pin "2") (pinfunction "P$2_2") (pintype "passive"))
      (node (ref "U2") (pin "1") (pinfunction "L1_1") (pintype "input"))
    )
    (net (code "62") (name "Net-(L2-P$1)") (class "Default")
      (node (ref "L2") (pin "1") (pinfunction "P$1_1") (pintype "passive"))
      (node (ref "U1") (pin "10") (pinfunction "L2_10") (pintype "input"))
    )
    (net (code "63") (name "Net-(L2-P$2)") (class "Default")
      (node (ref "L2") (pin "2") (pinfunction "P$2_2") (pintype "passive"))
      (node (ref "U1") (pin "1") (pinfunction "L1_1") (pintype "input"))
    )
    (net (code "64") (name "Net-(L3-PadP$2)") (class "Default")
      (node (ref "L3") (pin "P$2") (pinfunction "P$2_P$2") (pintype "passive"))
      (node (ref "TERMINAL_A") (pin "1") (pinfunction "1_1") (pintype "passive"))
    )
    (net (code "65") (name "Net-(L4-PadP$2)") (class "Default")
      (node (ref "L4") (pin "P$2") (pinfunction "P$2_P$2") (pintype "passive"))
      (node (ref "TERMINAL_B") (pin "1") (pinfunction "1_1") (pintype "passive"))
    )
    (net (code "66") (name "Net-(LED1-PadC)") (class "Default")
      (node (ref "LED1") (pin "C") (pinfunction "C_C") (pintype "passive"))
      (node (ref "R3") (pin "2") (pinfunction "2_2") (pintype "passive"))
    )
    (net (code "67") (name "Net-(LED2-PadC)") (class "Default")
      (node (ref "LED2") (pin "C") (pinfunction "C_C") (pintype "passive"))
      (node (ref "R4") (pin "2") (pinfunction "2_2") (pintype "passive"))
    )
    (net (code "68") (name "Net-(LED3-PadC)") (class "Default")
      (node (ref "LED3") (pin "C") (pinfunction "C_C") (pintype "passive"))
      (node (ref "R5") (pin "2") (pinfunction "2_2") (pintype "passive"))
    )
    (net (code "69") (name "Net-(LED4-PadC)") (class "Default")
      (node (ref "LED4") (pin "C") (pinfunction "C_C") (pintype "passive"))
      (node (ref "R6") (pin "2") (pinfunction "2_2") (pintype "passive"))
    )
    (net (code "70") (name "Net-(LED5-PadC)") (class "Default")
      (node (ref "LED5") (pin "C") (pinfunction "C_C") (pintype "passive"))
      (node (ref "R7") (pin "2") (pinfunction "2_2") (pintype "passive"))
    )
    (net (code "71") (name "Net-(LED6-PadC)") (class "Default")
      (node (ref "LED6") (pin "C") (pinfunction "C_C") (pintype "passive"))
      (node (ref "R8") (pin "2") (pinfunction "2_2") (pintype "passive"))
    )
    (net (code "72") (name "Net-(LED7-PadC)") (class "Default")
      (node (ref "LED7") (pin "C") (pinfunction "C_C") (pintype "passive"))
      (node (ref "R9") (pin "2") (pinfunction "2_2") (pintype "passive"))
    )
    (net (code "73") (name "Net-(LED8-PadC)") (class "Default")
      (node (ref "LED8") (pin "C") (pinfunction "C_C") (pintype "passive"))
      (node (ref "R10") (pin "2") (pinfunction "2_2") (pintype "passive"))
    )
    (net (code "74") (name "Net-(LED9-PadC)") (class "Default")
      (node (ref "LED9") (pin "C") (pinfunction "C_C") (pintype "passive"))
      (node (ref "R11") (pin "2") (pinfunction "2_2") (pintype "passive"))
    )
    (net (code "75") (name "Net-(Q1-B)") (class "Default")
      (node (ref "Q1") (pin "1") (pinfunction "B_1") (pintype "passive"))
      (node (ref "R13") (pin "1") (pinfunction "1_1") (pintype "passive"))
    )
    (net (code "76") (name "Net-(Q1-C)") (class "Default")
      (node (ref "BUZZ1") (pin "-") (pinfunction "-_-") (pintype "passive"))
      (node (ref "Q1") (pin "3") (pinfunction "C_3") (pintype "passive"))
    )
    (net (code "77") (name "Net-(U1-VAUX)") (class "Default")
      (node (ref "C5") (pin "1") (pinfunction "1_1") (pintype "passive"))
      (node (ref "U1") (pin "6") (pinfunction "VAUX_6") (pintype "passive"))
    )
    (net (code "78") (name "Net-(U2-VAUX)") (class "Default")
      (node (ref "C2") (pin "1") (pinfunction "1_1") (pintype "passive"))
      (node (ref "U2") (pin "6") (pinfunction "VAUX_6") (pintype "passive"))
    )
    (net (code "79") (name "Net-(U3-AOUT1)") (class "Default")
      (node (ref "C16") (pin "1") (pinfunction "1_1") (pintype "passive"))
      (node (ref "L3") (pin "P$1") (pinfunction "P$1_P$1") (pintype "passive"))
      (node (ref "U3") (pin "2") (pinfunction "AOUT1_2") (pintype "output"))
    )
    (net (code "80") (name "Net-(U3-AOUT2)") (class "Default")
      (node (ref "C16") (pin "2") (pinfunction "2_2") (pintype "passive"))
      (node (ref "TERMINAL_A") (pin "2") (pinfunction "2_2") (pintype "passive"))
      (node (ref "U3") (pin "4") (pinfunction "AOUT2_4") (pintype "output"))
    )
    (net (code "81") (name "Net-(U3-BOUT1)") (class "Default")
      (node (ref "C17") (pin "1") (pinfunction "1_1") (pintype "passive"))
      (node (ref "L4") (pin "P$1") (pinfunction "P$1_P$1") (pintype "passive"))
      (node (ref "U3") (pin "7") (pinfunction "BOUT1_7") (pintype "output"))
    )
    (net (code "82") (name "Net-(U3-BOUT2)") (class "Default")
      (node (ref "C17") (pin "2") (pinfunction "2_2") (pintype "passive"))
      (node (ref "TERMINAL_B") (pin "2") (pinfunction "2_2") (pintype "passive"))
      (node (ref "U3") (pin "5") (pinfunction "BOUT2_5") (pintype "output"))
    )
    (net (code "83") (name "Net-(U3-NSLEEP)") (class "Default")
      (node (ref "R1") (pin "1") (pinfunction "1_1") (pintype "passive"))
      (node (ref "U3") (pin "1") (pinfunction "NSLEEP_1") (pintype "input"))
    )
    (net (code "84") (name "Net-(U3-VCP)") (class "Default")
      (node (ref "C14") (pin "2") (pinfunction "2_2") (pintype "passive"))
      (node (ref "U3") (pin "11") (pinfunction "VCP_11") (pintype "bidirectional"))
    )
    (net (code "85") (name "Net-(U3-VINT)") (class "Default")
      (node (ref "C15") (pin "2") (pinfunction "2_2") (pintype "passive"))
      (node (ref "U3") (pin "14") (pinfunction "VINT_14") (pintype "power_in"))
    )
    (net (code "86") (name "Net-(U5-CPOUT)") (class "Default")
      (node (ref "C10") (pin "1") (pinfunction "1_1") (pintype "passive"))
      (node (ref "U5") (pin "20") (pinfunction "CPOUT_20") (pintype "bidirectional"))
    )
    (net (code "87") (name "Net-(U5-REGOUT)") (class "Default")
      (node (ref "C9") (pin "1") (pinfunction "1_1") (pintype "passive"))
      (node (ref "U5") (pin "10") (pinfunction "REGOUT_10") (pintype "bidirectional"))
    )
    (net (code "88") (name "Net-(U5-VDD)") (class "Default")
      (node (ref "C19") (pin "1") (pinfunction "1_1") (pintype "passive"))
      (node (ref "U5") (pin "13") (pinfunction "VDD_13") (pintype "bidirectional"))
      (node (ref "U5") (pin "8") (pinfunction "VLOGIC_8") (pintype "bidirectional"))
    )
    (net (code "89") (name "Net-(U6-Y)") (class "Default")
      (node (ref "R13") (pin "2") (pinfunction "2_2") (pintype "passive"))
      (node (ref "U6") (pin "4") (pinfunction "Y_4") (pintype "output"))
    )
    (net (code "90") (name "Net-(U7-(PCINT6{slash}XTAL1{slash}TOSC1)_PB6)") (class "Default")
      (node (ref "C12") (pin "2") (pinfunction "2_2") (pintype "passive"))
      (node (ref "U7") (pin "7") (pinfunction "(PCINT6/XTAL1/TOSC1)_PB6_7") (pintype "bidirectional"))
      (node (ref "Y1") (pin "2") (pinfunction "P$2_2") (pintype "passive"))
    )
    (net (code "91") (name "Net-(U7-(PCINT7{slash}XTAL2{slash}TOSC2)_PB7)") (class "Default")
      (node (ref "C13") (pin "2") (pinfunction "2_2") (pintype "passive"))
      (node (ref "U7") (pin "8") (pinfunction "(PCINT7/XTAL2/TOSC2)_PB7_8") (pintype "bidirectional"))
      (node (ref "Y1") (pin "1") (pinfunction "P$1_1") (pintype "passive"))
    )
    (net (code "92") (name "Net-(U9-CV)") (class "Default")
      (node (ref "C21") (pin "1") (pinfunction "1_1") (pintype "passive"))
      (node (ref "U9") (pin "5") (pinfunction "CV_5") (pintype "input"))
    )
    (net (code "93") (name "Net-(U9-DIS)") (class "Default")
      (node (ref "R20") (pin "3") (pinfunction "3_3") (pintype "passive"))
      (node (ref "R21") (pin "2") (pinfunction "2_2") (pintype "passive"))
      (node (ref "U9") (pin "7") (pinfunction "DIS_7") (pintype "input"))
    )
    (net (code "94") (name "Net-(U9-THR)") (class "Default")
      (node (ref "C20") (pin "1") (pinfunction "1_1") (pintype "passive"))
      (node (ref "R21") (pin "3") (pinfunction "3_3") (pintype "passive"))
      (node (ref "U9") (pin "2") (pinfunction "TR_2") (pintype "input"))
      (node (ref "U9") (pin "6") (pinfunction "THR_6") (pintype "input"))
    )
    (net (code "95") (name "VBAT") (class "Default")
      (node (ref "C1") (pin "1") (pinfunction "1_1") (pintype "passive"))
      (node (ref "C14") (pin "1") (pinfunction "1_1") (pintype "passive"))
      (node (ref "C4") (pin "1") (pinfunction "1_1") (pintype "passive"))
      (node (ref "R1") (pin "2") (pinfunction "2_2") (pintype "passive"))
      (node (ref "SW2") (pin "2") (pinfunction "2_2") (pintype "passive"))
      (node (ref "U1") (pin "2") (pinfunction "VIN_2") (pintype "power_in"))
      (node (ref "U1") (pin "3") (pinfunction "EN_3") (pintype "input"))
      (node (ref "U2") (pin "2") (pinfunction "VIN_2") (pintype "power_in"))
      (node (ref "U2") (pin "3") (pinfunction "EN_3") (pintype "input"))
      (node (ref "U3") (pin "12") (pinfunction "VM_12") (pintype "power_in"))
    )
    (net (code "96") (name "unconnected-(JP1-Pad2)") (class "Default")
      (node (ref "JP1") (pin "2") (pinfunction "2_2") (pintype "passive"))
    )
    (net (code "97") (name "unconnected-(JP1-Pad5)") (class "Default")
      (node (ref "JP1") (pin "5") (pinfunction "5_5") (pintype "passive"))
    )
    (net (code "98") (name "unconnected-(JP2-Pad5)") (class "Default")
      (node (ref "JP2") (pin "5") (pinfunction "5_5") (pintype "passive"))
    )
    (net (code "99") (name "unconnected-(JP2-Pad7)") (class "Default")
      (node (ref "JP2") (pin "7") (pinfunction "7_7") (pintype "passive"))
    )
    (net (code "100") (name "unconnected-(JP2-Pad8)") (class "Default")
      (node (ref "JP2") (pin "8") (pinfunction "8_8") (pintype "passive"))
    )
    (net (code "101") (name "unconnected-(JP2-Pad15)") (class "Default")
      (node (ref "JP2") (pin "15") (pinfunction "15_15") (pintype "passive"))
    )
    (net (code "102") (name "unconnected-(R20-Pad1)") (class "Default")
      (node (ref "R20") (pin "1") (pinfunction "1_1") (pintype "passive"))
    )
    (net (code "103") (name "unconnected-(R21-Pad1)") (class "Default")
      (node (ref "R21") (pin "1") (pinfunction "1_1") (pintype "passive"))
    )
    (net (code "104") (name "unconnected-(SW2-Pad1)") (class "Default")
      (node (ref "SW2") (pin "1") (pinfunction "1_1") (pintype "passive"))
    )
    (net (code "105") (name "unconnected-(U1-PG-Pad5)") (class "Default")
      (node (ref "U1") (pin "5") (pinfunction "PG_5") (pintype "output"))
    )
    (net (code "106") (name "unconnected-(U2-PG-Pad5)") (class "Default")
      (node (ref "U2") (pin "5") (pinfunction "PG_5") (pintype "output"))
    )
    (net (code "107") (name "unconnected-(U3-NFAULT-Pad8)") (class "Default")
      (node (ref "U3") (pin "8") (pinfunction "NFAULT_8") (pintype "output"))
    )
    (net (code "108") (name "unconnected-(U5-AUX_CL-Pad7)") (class "Default")
      (node (ref "U5") (pin "7") (pinfunction "AUX_CL_7") (pintype "bidirectional"))
    )
    (net (code "109") (name "unconnected-(U5-AUX_DA-Pad6)") (class "Default")
      (node (ref "U5") (pin "6") (pinfunction "AUX_DA_6") (pintype "bidirectional"))
    )
    (net (code "110") (name "unconnected-(U5-CLKIN-Pad1)") (class "Default")
      (node (ref "U5") (pin "1") (pinfunction "CLKIN_1") (pintype "bidirectional"))
    )
    (net (code "111") (name "unconnected-(U5-CLKOUT-Pad22)") (class "Default")
      (node (ref "U5") (pin "22") (pinfunction "CLKOUT_22") (pintype "bidirectional"))
    )
    (net (code "112") (name "unconnected-(U5-INT-Pad12)") (class "Default")
      (node (ref "U5") (pin "12") (pinfunction "INT_12") (pintype "bidirectional"))
    )
    (net (code "113") (name "unconnected-(U7-AREF-Pad20)") (class "Default")
      (node (ref "U7") (pin "20") (pinfunction "AREF_20") (pintype "passive"))
    )
  )
)
